# WATER-PUMP.net
KiCad netlist of a schematic drawn in Altium Designer
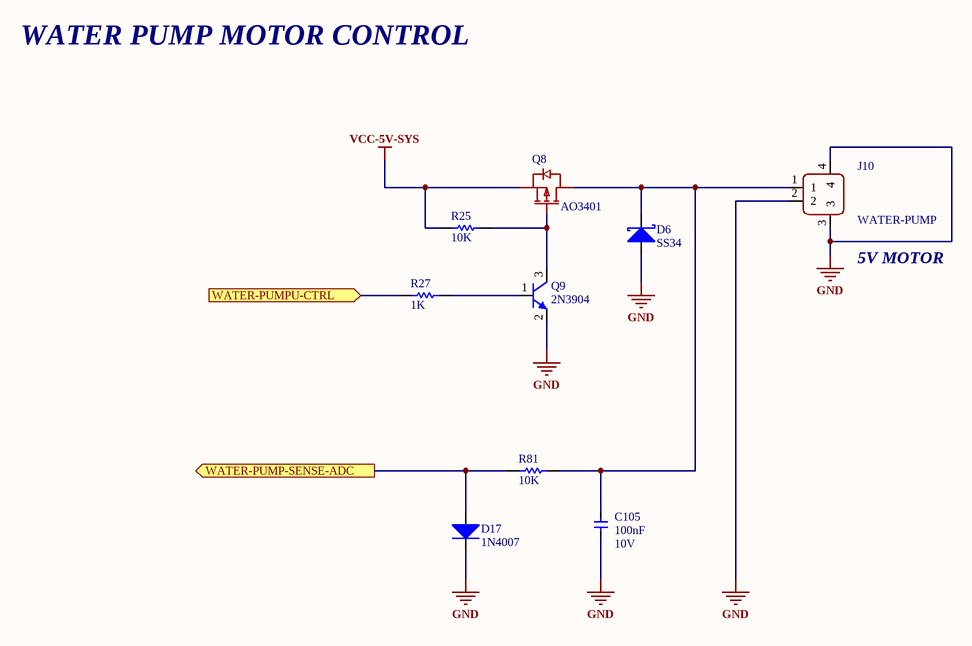
[diagram p0: WATER-PUMP .SchDoc]

(export (version "E")
  (design (tool "Eeschema 10.0.6"))
  (components
    (comp (ref "C105")
      (value "100nF")
      (footprint "CAP-0402")
      (fields (field (name "VOLTAGERATE") "10V"))
      (libsource (lib "DesignLibrary") (part "Capacitor-1"))
    )
    (comp (ref "D6") (value "SS34") (footprint "SMA") (libsource (lib "DesignLibrary") (part "DIODE-2")))
    (comp (ref "D17")
      (value "1N4007")
      (footprint "SOD123")
      (libsource (lib "DesignLibrary") (part "DIODE-1"))
    )
    (comp (ref "J10")
      (value "WATER-PUMP")
      (footprint "CONN-SMD_2P-P1.50_ZX-ZH1.5-2PWT")
      (description "ZX-ZH1.5-2PWT")
      (libsource (lib "DesignLibrary") (part "HDRx2"))
    )
    (comp (ref "Q8")
      (value "AO3401")
      (footprint "SOT23-3D")
      (libsource (lib "DesignLibrary") (part "P-MOS-SOT23"))
    )
    (comp (ref "Q9")
      (value "2N3904")
      (footprint "SOT23-3D")
      (libsource (lib "DesignLibrary") (part "NPN-SOT23"))
    )
    (comp (ref "R25")
      (value "10K")
      (footprint "RES-0402")
      (libsource (lib "DesignLibrary") (part "Resistor-1"))
    )
    (comp (ref "R27")
      (value "1K")
      (footprint "RES-0402")
      (libsource (lib "DesignLibrary") (part "Resistor-1"))
    )
    (comp (ref "R81")
      (value "10K")
      (footprint "RES-0402")
      (libsource (lib "DesignLibrary") (part "Resistor-1"))
    )
  )
  (nets
    (net (code "1") (name "/WATER-PUMP-SENSE-ADC") (class "Default")
      (node (ref "D17") (pin "1") (pinfunction "A_1") (pintype "passive"))
      (node (ref "R81") (pin "2") (pintype "passive"))
    )
    (net (code "2") (name "/WATER-PUMPU-CTRL") (class "Default")
      (node (ref "R27") (pin "2") (pintype "passive"))
    )
    (net (code "3") (name "GND") (class "Default")
      (node (ref "C105") (pin "1") (pinfunction "1_1") (pintype "passive"))
      (node (ref "D17") (pin "2") (pinfunction "K_2") (pintype "passive"))
      (node (ref "D6") (pin "1") (pinfunction "A_1") (pintype "passive"))
      (node (ref "J10") (pin "2") (pinfunction "2_2") (pintype "passive"))
      (node (ref "J10") (pin "3") (pinfunction "3_3") (pintype "passive"))
      (node (ref "J10") (pin "4") (pinfunction "4_4") (pintype "passive"))
      (node (ref "Q9") (pin "2") (pinfunction "E_2") (pintype "passive"))
    )
    (net (code "4") (name "Net-(D6-K)") (class "Default")
      (node (ref "C105") (pin "2") (pinfunction "2_2") (pintype "passive"))
      (node (ref "D6") (pin "2") (pinfunction "K_2") (pintype "passive"))
      (node (ref "J10") (pin "1") (pinfunction "1_1") (pintype "passive"))
      (node (ref "Q8") (pin "3") (pinfunction "D_3") (pintype "passive"))
      (node (ref "R81") (pin "1") (pintype "passive"))
    )
    (net (code "5") (name "Net-(Q8-G)") (class "Default")
      (node (ref "Q8") (pin "1") (pinfunction "G_1") (pintype "passive"))
      (node (ref "Q9") (pin "3") (pinfunction "C_3") (pintype "passive"))
      (node (ref "R25") (pin "1") (pintype "passive"))
    )
    (net (code "6") (name "Net-(Q9-B)") (class "Default")
      (node (ref "Q9") (pin "1") (pinfunction "B_1") (pintype "passive"))
      (node (ref "R27") (pin "1") (pintype "passive"))
    )
    (net (code "7") (name "VCC-5V-SYS") (class "Default")
      (node (ref "Q8") (pin "2") (pinfunction "S_2") (pintype "passive"))
      (node (ref "R25") (pin "2") (pintype "passive"))
    )
  )
)
